# cd_switching.net
KiCad netlist of a schematic drawn in Altium Designer
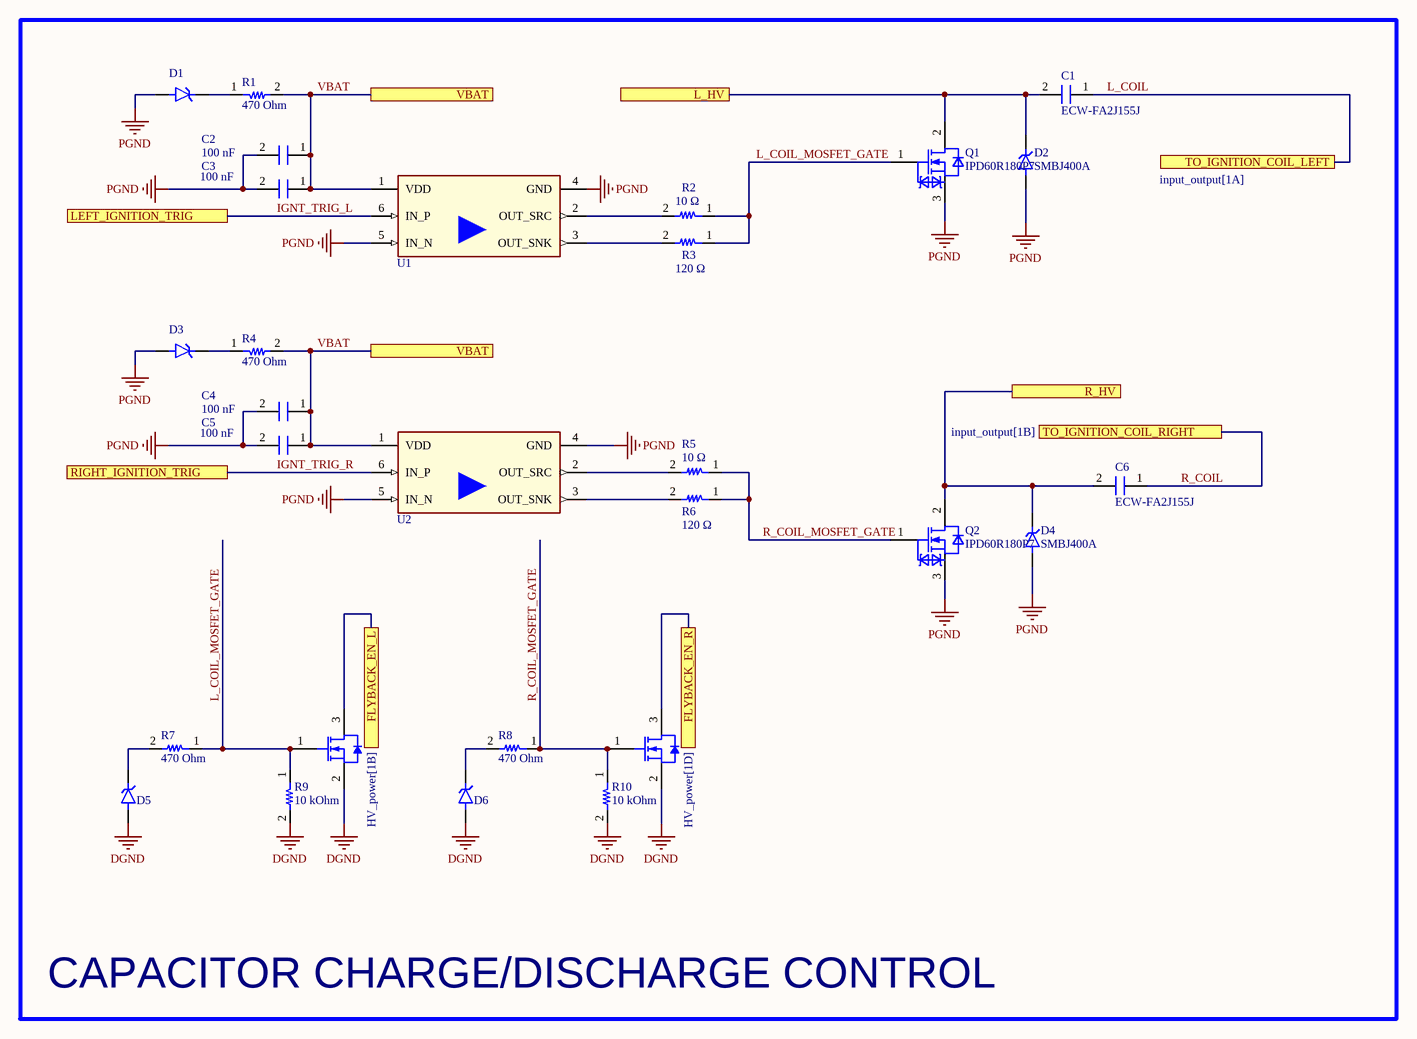
[diagram p0: cd_switching.SchDoc]

(export (version "E")
  (design (tool "Eeschema 10.0.6"))
  (components
    (comp (ref "C1")
      (value "ECW-FA2J155J")
      (footprint "22,5mm_CAP")
      (libsource (lib "RC_sch") (part "Capacitor_THT_22.5mm"))
    )
    (comp (ref "C2")
      (value "100 nF")
      (footprint "0603_FP")
      (fields (field (name "Comment") "Capacitor_0603"))
      (libsource (lib "RC_sch") (part "Capacitor_0603"))
    )
    (comp (ref "C3")
      (value "100 nF")
      (footprint "0603_FP")
      (fields (field (name "Comment") "Capacitor_0603"))
      (libsource (lib "RC_sch") (part "Capacitor_0603"))
    )
    (comp (ref "C4")
      (value "100 nF")
      (footprint "0603_FP")
      (fields (field (name "Comment") "Capacitor_0603"))
      (libsource (lib "RC_sch") (part "Capacitor_0603"))
    )
    (comp (ref "C5")
      (value "100 nF")
      (footprint "0603_FP")
      (fields (field (name "Comment") "Capacitor_0603"))
      (libsource (lib "RC_sch") (part "Capacitor_0603"))
    )
    (comp (ref "C6")
      (value "ECW-FA2J155J")
      (footprint "22,5mm_CAP")
      (libsource (lib "RC_sch") (part "Capacitor_THT_22.5mm"))
    )
    (comp (ref "D1")
      (value "BZT52B15SH_RRG")
      (footprint "DIO_BZT52B15SH_RRG")
      (description "SOD-323, 200mW, 2%, 15V, Zener Diode")
      (fields (field (name "MF") "Taiwan Semiconductor Corporation") (field (name "MP") "BZT52B15SH RRG"))
      (libsource (lib "BZT52B15SH_RRG") (part "BZT52B15SH_RRG"))
    )
    (comp (ref "D2")
      (value "SMBJ400A")
      (footprint "DIOM5436X261N")
      (description "Pince 648V 900mA Ipp TVS Diode Surface Mount DO-214AA (SMBJ)")
      (fields (field (name "MF") "Littelfuse"))
      (libsource (lib "SMBJ400A") (part "SMBJ400A"))
    )
    (comp (ref "D3")
      (value "BZT52B15SH_RRG")
      (footprint "DIO_BZT52B15SH_RRG")
      (description "SOD-323, 200mW, 2%, 15V, Zener Diode")
      (fields (field (name "MF") "Taiwan Semiconductor Corporation") (field (name "MP") "BZT52B15SH RRG"))
      (libsource (lib "BZT52B15SH_RRG") (part "BZT52B15SH_RRG"))
    )
    (comp (ref "D4")
      (value "SMBJ400A")
      (footprint "DIOM5436X261N")
      (description "Pince 648V 900mA Ipp TVS Diode Surface Mount DO-214AA (SMBJ)")
      (fields (field (name "MF") "Littelfuse"))
      (libsource (lib "SMBJ400A") (part "SMBJ400A"))
    )
    (comp (ref "D5")
      (value "BZT52B15SH_RRG")
      (footprint "DIO_BZT52B15SH_RRG")
      (description "SOD-323, 200mW, 2%, 15V, Zener Diode")
      (fields (field (name "MF") "Taiwan Semiconductor Corporation") (field (name "MP") "BZT52B15SH RRG"))
      (libsource (lib "BZT52B15SH_RRG") (part "BZT52B15SH_RRG"))
    )
    (comp (ref "D6")
      (value "BZT52B15SH_RRG")
      (footprint "DIO_BZT52B15SH_RRG")
      (description "SOD-323, 200mW, 2%, 15V, Zener Diode")
      (fields (field (name "MF") "Taiwan Semiconductor Corporation") (field (name "MP") "BZT52B15SH RRG"))
      (libsource (lib "BZT52B15SH_RRG") (part "BZT52B15SH_RRG"))
    )
    (comp (ref "Q1")
      (value "IPD60R180P7")
      (footprint "DPAK228P987X240-3N")
      (fields (field (name "MANUFACTURER") "Infineon Technologies"))
      (libsource (lib "IPD60R180P7") (part "IPD60R180P7"))
    )
    (comp (ref "Q2")
      (value "IPD60R180P7")
      (footprint "DPAK228P987X240-3N")
      (fields (field (name "MANUFACTURER") "Infineon Technologies"))
      (libsource (lib "IPD60R180P7") (part "IPD60R180P7"))
    )
    (comp (ref "Q3")
      (value "MGSF1N03LT1G")
      (footprint "ONSC-SOT-23-3-318-08_V")
      (description "Power MOSFET, 30 V, 2.1 A, Single N-Channel, 3-Pin SOT-23, Pb-Free, Tape and Reel")
      (fields (field (name "MANUFACTURER") "On Semiconductor"))
      (libsource (lib "Altium Content Vault") (part "ONSC-NMOS-G1S2D3-3"))
    )
    (comp (ref "Q4")
      (value "MGSF1N03LT1G")
      (footprint "ONSC-SOT-23-3-318-08_V")
      (description "Power MOSFET, 30 V, 2.1 A, Single N-Channel, 3-Pin SOT-23, Pb-Free, Tape and Reel")
      (fields (field (name "MANUFACTURER") "On Semiconductor"))
      (libsource (lib "Altium Content Vault") (part "ONSC-NMOS-G1S2D3-3"))
    )
    (comp (ref "R1")
      (value "470 Ohm")
      (footprint "0603_FP")
      (fields (field (name "Comment") "Resistor_0603"))
      (libsource (lib "RC_sch") (part "Resistor_0603"))
    )
    (comp (ref "R2")
      (value "10 Ω")
      (footprint "0603_FP")
      (fields (field (name "Comment") "Resistor_0603"))
      (libsource (lib "RC_sch") (part "Resistor_0603"))
    )
    (comp (ref "R3")
      (value "120 Ω")
      (footprint "0603_FP")
      (fields (field (name "Comment") "Resistor_0603"))
      (libsource (lib "RC_sch") (part "Resistor_0603"))
    )
    (comp (ref "R4")
      (value "470 Ohm")
      (footprint "0603_FP")
      (fields (field (name "Comment") "Resistor_0603"))
      (libsource (lib "RC_sch") (part "Resistor_0603"))
    )
    (comp (ref "R5")
      (value "10 Ω")
      (footprint "0603_FP")
      (fields (field (name "Comment") "Resistor_0603"))
      (libsource (lib "RC_sch") (part "Resistor_0603"))
    )
    (comp (ref "R6")
      (value "120 Ω")
      (footprint "0603_FP")
      (fields (field (name "Comment") "Resistor_0603"))
      (libsource (lib "RC_sch") (part "Resistor_0603"))
    )
    (comp (ref "R7")
      (value "470 Ohm")
      (footprint "0603_FP")
      (fields (field (name "Comment") "Resistor_0603"))
      (libsource (lib "RC_sch") (part "Resistor_0603"))
    )
    (comp (ref "R8")
      (value "470 Ohm")
      (footprint "0603_FP")
      (fields (field (name "Comment") "Resistor_0603"))
      (libsource (lib "RC_sch") (part "Resistor_0603"))
    )
    (comp (ref "R9")
      (value "10 kOhm")
      (footprint "0402_fp")
      (fields (field (name "Comment") "Resistor_0402"))
      (libsource (lib "RC_sch") (part "Resistor_0402"))
    )
    (comp (ref "R10")
      (value "10 kOhm")
      (footprint "0402_fp")
      (fields (field (name "Comment") "Resistor_0402"))
      (libsource (lib "RC_sch") (part "Resistor_0402"))
    )
    (comp (ref "U1")
      (value "1EDN7511B")
      (footprint "SOT95P280X145-6N-7-V")
      (description "EiceDRIVER, Fast Single Channel 4A/8A Low-Side Gate Driver, UVLO - 4.2V")
      (fields (field (name "MANUFACTURER") "Infineon Technologies"))
      (libsource (lib "1EDN7511B") (part "1EDN7511B"))
    )
    (comp (ref "U2")
      (value "1EDN7511B")
      (footprint "SOT95P280X145-6N-7-V")
      (description "EiceDRIVER, Fast Single Channel 4A/8A Low-Side Gate Driver, UVLO - 4.2V")
      (fields (field (name "MANUFACTURER") "Infineon Technologies"))
      (libsource (lib "1EDN7511B") (part "1EDN7511B"))
    )
  )
  (nets
    (net (code "1") (name "/FLYBACK_EN_L") (class "Default")
      (node (ref "Q3") (pin "3") (pinfunction "D_3") (pintype "passive"))
    )
    (net (code "2") (name "/FLYBACK_EN_R") (class "Default")
      (node (ref "Q4") (pin "3") (pinfunction "D_3") (pintype "passive"))
    )
    (net (code "3") (name "/IGNT_TRIG_L") (class "Default")
      (node (ref "U1") (pin "6") (pinfunction "IN_P_6") (pintype "input"))
    )
    (net (code "4") (name "/IGNT_TRIG_R") (class "Default")
      (node (ref "U2") (pin "6") (pinfunction "IN_P_6") (pintype "input"))
    )
    (net (code "5") (name "/L_COIL") (class "Default")
      (node (ref "C1") (pin "1") (pinfunction "1_1") (pintype "passive"))
    )
    (net (code "6") (name "/L_COIL_MOSFET_GATE") (class "Default")
      (node (ref "Q1") (pin "1") (pinfunction "GATE_1") (pintype "passive"))
      (node (ref "Q3") (pin "1") (pinfunction "G_1") (pintype "passive"))
      (node (ref "R2") (pin "1") (pinfunction "1_1") (pintype "passive"))
      (node (ref "R3") (pin "1") (pinfunction "1_1") (pintype "passive"))
      (node (ref "R7") (pin "1") (pinfunction "1_1") (pintype "passive"))
      (node (ref "R9") (pin "1") (pinfunction "1_1") (pintype "passive"))
    )
    (net (code "7") (name "/L_HV") (class "Default")
      (node (ref "C1") (pin "2") (pinfunction "2_2") (pintype "passive"))
      (node (ref "D2") (pin "1") (pinfunction "K_1") (pintype "passive"))
      (node (ref "Q1") (pin "2") (pinfunction "DRAIN_2") (pintype "passive"))
    )
    (net (code "8") (name "/R_COIL") (class "Default")
      (node (ref "C6") (pin "1") (pinfunction "1_1") (pintype "passive"))
    )
    (net (code "9") (name "/R_COIL_MOSFET_GATE") (class "Default")
      (node (ref "Q2") (pin "1") (pinfunction "GATE_1") (pintype "passive"))
      (node (ref "Q4") (pin "1") (pinfunction "G_1") (pintype "passive"))
      (node (ref "R10") (pin "1") (pinfunction "1_1") (pintype "passive"))
      (node (ref "R5") (pin "1") (pinfunction "1_1") (pintype "passive"))
      (node (ref "R6") (pin "1") (pinfunction "1_1") (pintype "passive"))
      (node (ref "R8") (pin "1") (pinfunction "1_1") (pintype "passive"))
    )
    (net (code "10") (name "/R_HV") (class "Default")
      (node (ref "C6") (pin "2") (pinfunction "2_2") (pintype "passive"))
      (node (ref "D4") (pin "1") (pinfunction "K_1") (pintype "passive"))
      (node (ref "Q2") (pin "2") (pinfunction "DRAIN_2") (pintype "passive"))
    )
    (net (code "11") (name "/VBAT") (class "Default")
      (node (ref "C2") (pin "1") (pinfunction "1_1") (pintype "passive"))
      (node (ref "C3") (pin "1") (pinfunction "1_1") (pintype "passive"))
      (node (ref "C4") (pin "1") (pinfunction "1_1") (pintype "passive"))
      (node (ref "C5") (pin "1") (pinfunction "1_1") (pintype "passive"))
      (node (ref "R1") (pin "2") (pinfunction "2_2") (pintype "passive"))
      (node (ref "R4") (pin "2") (pinfunction "2_2") (pintype "passive"))
      (node (ref "U1") (pin "1") (pinfunction "VDD_1") (pintype "power_in"))
      (node (ref "U2") (pin "1") (pinfunction "VDD_1") (pintype "power_in"))
    )
    (net (code "12") (name "DGND") (class "Default")
      (node (ref "D5") (pin "2") (pinfunction "A_2") (pintype "passive"))
      (node (ref "D6") (pin "2") (pinfunction "A_2") (pintype "passive"))
      (node (ref "Q3") (pin "2") (pinfunction "S_2") (pintype "passive"))
      (node (ref "Q4") (pin "2") (pinfunction "S_2") (pintype "passive"))
      (node (ref "R10") (pin "2") (pinfunction "2_2") (pintype "passive"))
      (node (ref "R9") (pin "2") (pinfunction "2_2") (pintype "passive"))
    )
    (net (code "13") (name "Net-(D1-K)") (class "Default")
      (node (ref "D1") (pin "1") (pinfunction "K_1") (pintype "passive"))
      (node (ref "R1") (pin "1") (pinfunction "1_1") (pintype "passive"))
    )
    (net (code "14") (name "Net-(D3-K)") (class "Default")
      (node (ref "D3") (pin "1") (pinfunction "K_1") (pintype "passive"))
      (node (ref "R4") (pin "1") (pinfunction "1_1") (pintype "passive"))
    )
    (net (code "15") (name "Net-(D5-K)") (class "Default")
      (node (ref "D5") (pin "1") (pinfunction "K_1") (pintype "passive"))
      (node (ref "R7") (pin "2") (pinfunction "2_2") (pintype "passive"))
    )
    (net (code "16") (name "Net-(D6-K)") (class "Default")
      (node (ref "D6") (pin "1") (pinfunction "K_1") (pintype "passive"))
      (node (ref "R8") (pin "2") (pinfunction "2_2") (pintype "passive"))
    )
    (net (code "17") (name "Net-(U1-OUT_SNK)") (class "Default")
      (node (ref "R3") (pin "2") (pinfunction "2_2") (pintype "passive"))
      (node (ref "U1") (pin "3") (pinfunction "OUT_SNK_3") (pintype "output"))
    )
    (net (code "18") (name "Net-(U1-OUT_SRC)") (class "Default")
      (node (ref "R2") (pin "2") (pinfunction "2_2") (pintype "passive"))
      (node (ref "U1") (pin "2") (pinfunction "OUT_SRC_2") (pintype "output"))
    )
    (net (code "19") (name "Net-(U2-OUT_SNK)") (class "Default")
      (node (ref "R6") (pin "2") (pinfunction "2_2") (pintype "passive"))
      (node (ref "U2") (pin "3") (pinfunction "OUT_SNK_3") (pintype "output"))
    )
    (net (code "20") (name "Net-(U2-OUT_SRC)") (class "Default")
      (node (ref "R5") (pin "2") (pinfunction "2_2") (pintype "passive"))
      (node (ref "U2") (pin "2") (pinfunction "OUT_SRC_2") (pintype "output"))
    )
    (net (code "21") (name "PGND") (class "Default")
      (node (ref "C2") (pin "2") (pinfunction "2_2") (pintype "passive"))
      (node (ref "C3") (pin "2") (pinfunction "2_2") (pintype "passive"))
      (node (ref "C4") (pin "2") (pinfunction "2_2") (pintype "passive"))
      (node (ref "C5") (pin "2") (pinfunction "2_2") (pintype "passive"))
      (node (ref "D1") (pin "2") (pinfunction "A_2") (pintype "passive"))
      (node (ref "D2") (pin "2") (pinfunction "A_2") (pintype "passive"))
      (node (ref "D3") (pin "2") (pinfunction "A_2") (pintype "passive"))
      (node (ref "D4") (pin "2") (pinfunction "A_2") (pintype "passive"))
      (node (ref "Q1") (pin "3") (pinfunction "SOURCE_3") (pintype "passive"))
      (node (ref "Q2") (pin "3") (pinfunction "SOURCE_3") (pintype "passive"))
      (node (ref "U1") (pin "4") (pinfunction "GND_4") (pintype "power_in"))
      (node (ref "U1") (pin "5") (pinfunction "IN_N_5") (pintype "input"))
      (node (ref "U2") (pin "4") (pinfunction "GND_4") (pintype "power_in"))
      (node (ref "U2") (pin "5") (pinfunction "IN_N_5") (pintype "input"))
    )
  )
)
